# Motor_Driver2.net
KiCad netlist of a schematic drawn in EAGLE
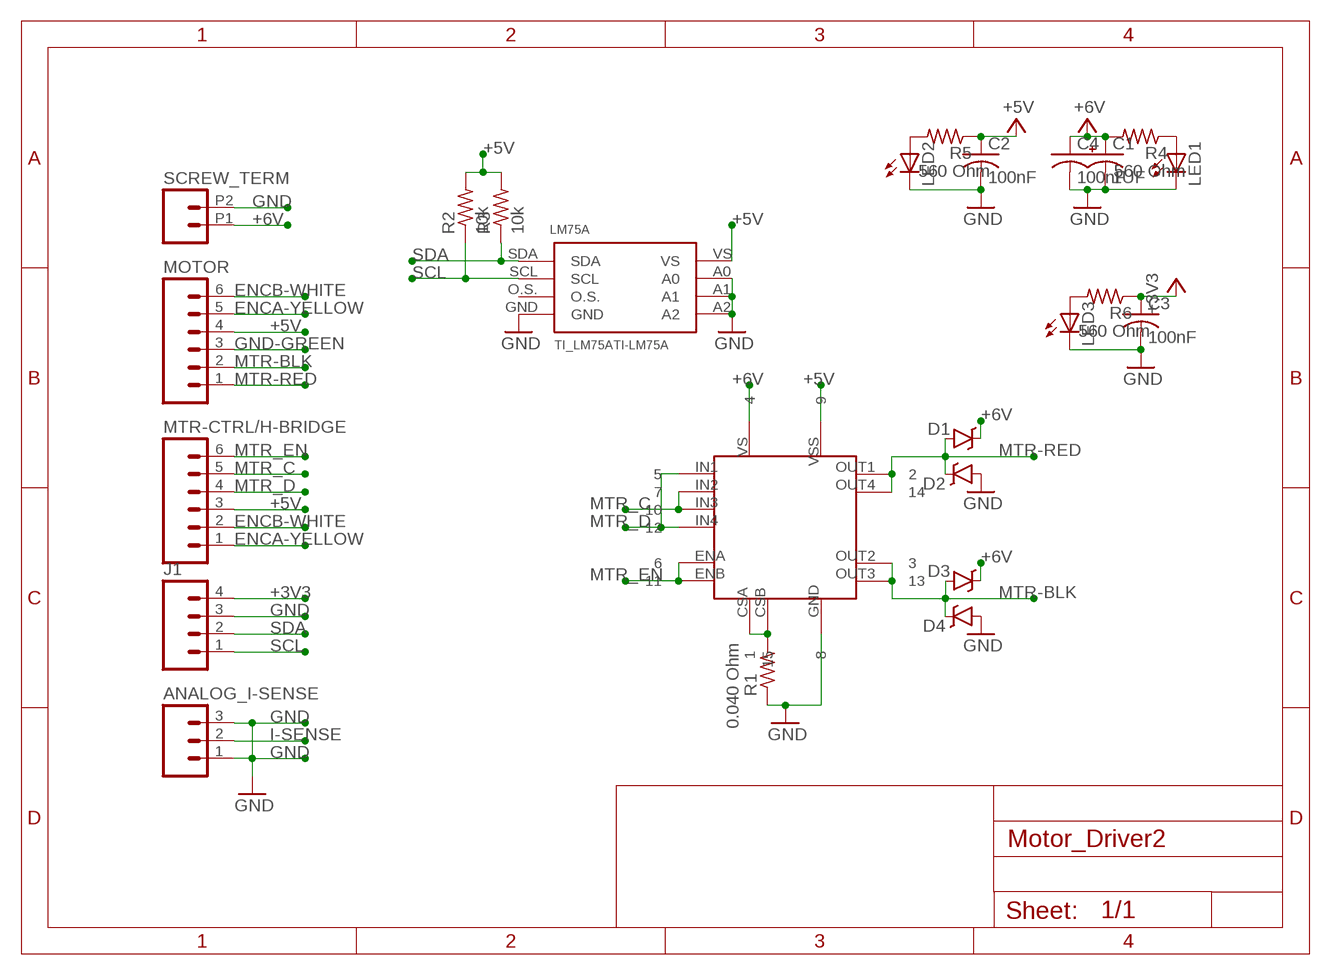
[diagram p0: schematic, sheet 1]

(export (version "E")
  (design (tool "Eeschema 10.0.6"))
  (components
    (comp (ref "ANALOG_I-SENSE")
      (value "M03PTH")
      (footprint "eagle-import:1X03")
      (libsource (lib "eagle-import") (part "M03PTH"))
    )
    (comp (ref "C1")
      (value "1UF")
      (footprint "eagle-import:CPOL-RADIAL-1UF-50V-KIT")
      (libsource (lib "eagle-import") (part "1UF-50V-20%(PTH)KIT"))
    )
    (comp (ref "C2")
      (value "100nF")
      (footprint "eagle-import:C1206")
      (libsource (lib "eagle-import") (part "C-USC1206"))
    )
    (comp (ref "C3")
      (value "100nF")
      (footprint "eagle-import:C1206")
      (libsource (lib "eagle-import") (part "C-USC1206"))
    )
    (comp (ref "C4")
      (value "100nF")
      (footprint "eagle-import:C1206")
      (libsource (lib "eagle-import") (part "C-USC1206"))
    )
    (comp (ref "D1")
      (value "B340A")
      (footprint "eagle-import:SMA-DIODE")
      (libsource (lib "eagle-import") (part "DIODE-SCHOTTKY-B340A"))
    )
    (comp (ref "D2")
      (value "B340A")
      (footprint "eagle-import:SMA-DIODE")
      (libsource (lib "eagle-import") (part "DIODE-SCHOTTKY-B340A"))
    )
    (comp (ref "D3")
      (value "B340A")
      (footprint "eagle-import:SMA-DIODE")
      (libsource (lib "eagle-import") (part "DIODE-SCHOTTKY-B340A"))
    )
    (comp (ref "D4")
      (value "B340A")
      (footprint "eagle-import:SMA-DIODE")
      (libsource (lib "eagle-import") (part "DIODE-SCHOTTKY-B340A"))
    )
    (comp (ref "J1")
      (value "M04PTH")
      (footprint "eagle-import:1X04")
      (libsource (lib "eagle-import") (part "M04PTH"))
    )
    (comp (ref "LED1")
      (value "LEDSMT1206")
      (footprint "eagle-import:1206")
      (libsource (lib "eagle-import") (part "LEDSMT1206"))
    )
    (comp (ref "LED2")
      (value "LEDSMT1206")
      (footprint "eagle-import:1206")
      (libsource (lib "eagle-import") (part "LEDSMT1206"))
    )
    (comp (ref "LED3")
      (value "LEDSMT1206")
      (footprint "eagle-import:1206")
      (libsource (lib "eagle-import") (part "LEDSMT1206"))
    )
    (comp (ref "LM75A")
      (value "TI_LM75ATI-LM75A")
      (footprint "eagle-import:TI_LM75A")
      (libsource (lib "eagle-import") (part "TI_LM75ATI-LM75A"))
    )
    (comp (ref "MOTOR")
      (value "M06SILK_FEMALE_PTH")
      (footprint "eagle-import:1X06")
      (libsource (lib "eagle-import") (part "M06SILK_FEMALE_PTH"))
    )
    (comp (ref "MTR-CTRL/H-BRIDGE")
      (value "M06SILK_FEMALE_PTH")
      (footprint "eagle-import:1X06")
      (libsource (lib "eagle-import") (part "M06SILK_FEMALE_PTH"))
    )
    (comp (ref "R1")
      (value "0.040 Ohm")
      (footprint "eagle-import:M0805")
      (libsource (lib "eagle-import") (part "R-US_M0805"))
    )
    (comp (ref "R2")
      (value "10k")
      (footprint "eagle-import:M1206")
      (libsource (lib "eagle-import") (part "R-US_M1206"))
    )
    (comp (ref "R3")
      (value "10k")
      (footprint "eagle-import:M1206")
      (libsource (lib "eagle-import") (part "R-US_M1206"))
    )
    (comp (ref "R4")
      (value "560 Ohm")
      (footprint "eagle-import:M0805")
      (libsource (lib "eagle-import") (part "R-US_M0805"))
    )
    (comp (ref "R5")
      (value "560 Ohm")
      (footprint "eagle-import:M0805")
      (libsource (lib "eagle-import") (part "R-US_M0805"))
    )
    (comp (ref "R6")
      (value "560 Ohm")
      (footprint "eagle-import:M0805")
      (libsource (lib "eagle-import") (part "R-US_M0805"))
    )
    (comp (ref "SCREW_TERM")
      (value "M022.54MM_SCREWTERM")
      (footprint "eagle-import:1X02_2.54_SCREWTERM")
      (libsource (lib "eagle-import") (part "M022.54MM_SCREWTERM"))
    )
    (comp (ref "U$1")
      (value "STL298N")
      (footprint "eagle-import:STL298N")
      (libsource (lib "eagle-import") (part "STL298N"))
    )
  )
  (nets
    (net (code "1") (name "+3V3") (class "Default")
      (node (ref "C3") (pin "1") (pinfunction "1_1") (pintype "passive"))
      (node (ref "J1") (pin "4") (pinfunction "4_4") (pintype "passive"))
      (node (ref "R6") (pin "1") (pinfunction "1_1") (pintype "passive"))
    )
    (net (code "2") (name "+5V") (class "Default")
      (node (ref "C2") (pin "1") (pinfunction "1_1") (pintype "passive"))
      (node (ref "LM75A") (pin "VS") (pinfunction "VS_VS") (pintype "bidirectional"))
      (node (ref "MOTOR") (pin "4") (pinfunction "4_4") (pintype "passive"))
      (node (ref "MTR-CTRL/H-BRIDGE") (pin "3") (pinfunction "3_3") (pintype "passive"))
      (node (ref "R2") (pin "2") (pinfunction "2_2") (pintype "passive"))
      (node (ref "R3") (pin "2") (pinfunction "2_2") (pintype "passive"))
      (node (ref "R5") (pin "1") (pinfunction "1_1") (pintype "passive"))
    )
    (net (code "3") (name "+6V") (class "Default")
      (node (ref "C1") (pin "1") (pinfunction "+_1") (pintype "passive"))
      (node (ref "C4") (pin "1") (pinfunction "1_1") (pintype "passive"))
      (node (ref "D1") (pin "C") (pinfunction "C_C") (pintype "passive"))
      (node (ref "D3") (pin "C") (pinfunction "C_C") (pintype "passive"))
      (node (ref "R4") (pin "2") (pinfunction "2_2") (pintype "passive"))
      (node (ref "SCREW_TERM") (pin "P1") (pinfunction "1_P1") (pintype "passive"))
    )
    (net (code "4") (name "/ENCA-YELLOW") (class "Default")
      (node (ref "MOTOR") (pin "5") (pinfunction "5_5") (pintype "passive"))
      (node (ref "MTR-CTRL/H-BRIDGE") (pin "1") (pinfunction "1_1") (pintype "passive"))
    )
    (net (code "5") (name "/ENCB-WHITE") (class "Default")
      (node (ref "MOTOR") (pin "6") (pinfunction "6_6") (pintype "passive"))
      (node (ref "MTR-CTRL/H-BRIDGE") (pin "2") (pinfunction "2_2") (pintype "passive"))
    )
    (net (code "6") (name "/GND-GREEN") (class "Default")
      (node (ref "MOTOR") (pin "3") (pinfunction "3_3") (pintype "passive"))
    )
    (net (code "7") (name "/I-SENSE") (class "Default")
      (node (ref "ANALOG_I-SENSE") (pin "2") (pinfunction "2_2") (pintype "passive"))
    )
    (net (code "8") (name "/MTR-BLK") (class "Default")
      (node (ref "D3") (pin "A") (pinfunction "A_A") (pintype "passive"))
      (node (ref "D4") (pin "C") (pinfunction "C_C") (pintype "passive"))
      (node (ref "MOTOR") (pin "2") (pinfunction "2_2") (pintype "passive"))
    )
    (net (code "9") (name "/MTR-RED") (class "Default")
      (node (ref "D1") (pin "A") (pinfunction "A_A") (pintype "passive"))
      (node (ref "D2") (pin "C") (pinfunction "C_C") (pintype "passive"))
      (node (ref "MOTOR") (pin "1") (pinfunction "1_1") (pintype "passive"))
    )
    (net (code "10") (name "/MTR_C") (class "Default")
      (node (ref "MTR-CTRL/H-BRIDGE") (pin "5") (pinfunction "5_5") (pintype "passive"))
    )
    (net (code "11") (name "/MTR_D") (class "Default")
      (node (ref "MTR-CTRL/H-BRIDGE") (pin "4") (pinfunction "4_4") (pintype "passive"))
    )
    (net (code "12") (name "/MTR_EN") (class "Default")
      (node (ref "MTR-CTRL/H-BRIDGE") (pin "6") (pinfunction "6_6") (pintype "passive"))
    )
    (net (code "13") (name "/SCL") (class "Default")
      (node (ref "J1") (pin "1") (pinfunction "1_1") (pintype "passive"))
      (node (ref "LM75A") (pin "SCL") (pinfunction "SCL_SCL") (pintype "bidirectional"))
      (node (ref "R2") (pin "1") (pinfunction "1_1") (pintype "passive"))
    )
    (net (code "14") (name "/SDA") (class "Default")
      (node (ref "J1") (pin "2") (pinfunction "2_2") (pintype "passive"))
      (node (ref "LM75A") (pin "SDA") (pinfunction "SDA_SDA") (pintype "bidirectional"))
      (node (ref "R3") (pin "1") (pinfunction "1_1") (pintype "passive"))
    )
    (net (code "15") (name "GND") (class "Default")
      (node (ref "ANALOG_I-SENSE") (pin "1") (pinfunction "1_1") (pintype "passive"))
      (node (ref "ANALOG_I-SENSE") (pin "3") (pinfunction "3_3") (pintype "passive"))
      (node (ref "C1") (pin "2") (pinfunction "-_2") (pintype "passive"))
      (node (ref "C2") (pin "2") (pinfunction "2_2") (pintype "passive"))
      (node (ref "C3") (pin "2") (pinfunction "2_2") (pintype "passive"))
      (node (ref "C4") (pin "2") (pinfunction "2_2") (pintype "passive"))
      (node (ref "D2") (pin "A") (pinfunction "A_A") (pintype "passive"))
      (node (ref "D4") (pin "A") (pinfunction "A_A") (pintype "passive"))
      (node (ref "J1") (pin "3") (pinfunction "3_3") (pintype "passive"))
      (node (ref "LED1") (pin "C") (pinfunction "C_C") (pintype "passive"))
      (node (ref "LED2") (pin "C") (pinfunction "C_C") (pintype "passive"))
      (node (ref "LED3") (pin "C") (pinfunction "C_C") (pintype "passive"))
      (node (ref "LM75A") (pin "A0") (pinfunction "A0_A0") (pintype "bidirectional"))
      (node (ref "LM75A") (pin "A1") (pinfunction "A1_A1") (pintype "bidirectional"))
      (node (ref "LM75A") (pin "A2") (pinfunction "A2_A2") (pintype "bidirectional"))
      (node (ref "LM75A") (pin "GND") (pinfunction "GND_GND") (pintype "bidirectional"))
      (node (ref "R1") (pin "1") (pinfunction "1_1") (pintype "passive"))
      (node (ref "SCREW_TERM") (pin "P2") (pinfunction "2_P2") (pintype "passive"))
    )
    (net (code "16") (name "Net-(LED1-PadA)") (class "Default")
      (node (ref "LED1") (pin "A") (pinfunction "A_A") (pintype "passive"))
      (node (ref "R4") (pin "1") (pinfunction "1_1") (pintype "passive"))
    )
    (net (code "17") (name "Net-(LED2-PadA)") (class "Default")
      (node (ref "LED2") (pin "A") (pinfunction "A_A") (pintype "passive"))
      (node (ref "R5") (pin "2") (pinfunction "2_2") (pintype "passive"))
    )
    (net (code "18") (name "Net-(LED3-PadA)") (class "Default")
      (node (ref "LED3") (pin "A") (pinfunction "A_A") (pintype "passive"))
      (node (ref "R6") (pin "2") (pinfunction "2_2") (pintype "passive"))
    )
    (net (code "19") (name "unconnected-(LM75A-PadO.S.)") (class "Default")
      (node (ref "LM75A") (pin "O.S.") (pinfunction "O.S._O.S.") (pintype "bidirectional"))
    )
    (net (code "20") (name "unconnected-(R1-Pad2)") (class "Default")
      (node (ref "R1") (pin "2") (pinfunction "2_2") (pintype "passive"))
    )
    (net (code "21") (name "unconnected-(U$1-1-PadCSA)") (class "Default")
      (node (ref "U$1") (pin "CSA") (pinfunction "1_CSA") (pintype "bidirectional"))
    )
    (net (code "22") (name "unconnected-(U$1-2-PadOUT1)") (class "Default")
      (node (ref "U$1") (pin "OUT1") (pinfunction "2_OUT1") (pintype "bidirectional"))
    )
    (net (code "23") (name "unconnected-(U$1-3-PadOUT2)") (class "Default")
      (node (ref "U$1") (pin "OUT2") (pinfunction "3_OUT2") (pintype "bidirectional"))
    )
    (net (code "24") (name "unconnected-(U$1-4-PadVS)") (class "Default")
      (node (ref "U$1") (pin "VS") (pinfunction "4_VS") (pintype "bidirectional"))
    )
    (net (code "25") (name "unconnected-(U$1-5-PadIN1)") (class "Default")
      (node (ref "U$1") (pin "IN1") (pinfunction "5_IN1") (pintype "bidirectional"))
    )
    (net (code "26") (name "unconnected-(U$1-6-PadENA)") (class "Default")
      (node (ref "U$1") (pin "ENA") (pinfunction "6_ENA") (pintype "bidirectional"))
    )
    (net (code "27") (name "unconnected-(U$1-7-PadIN2)") (class "Default")
      (node (ref "U$1") (pin "IN2") (pinfunction "7_IN2") (pintype "bidirectional"))
    )
    (net (code "28") (name "unconnected-(U$1-8-PadGND)") (class "Default")
      (node (ref "U$1") (pin "GND") (pinfunction "8_GND") (pintype "bidirectional"))
    )
    (net (code "29") (name "unconnected-(U$1-9-PadVSS)") (class "Default")
      (node (ref "U$1") (pin "VSS") (pinfunction "9_VSS") (pintype "bidirectional"))
    )
    (net (code "30") (name "unconnected-(U$1-10-PadIN3)") (class "Default")
      (node (ref "U$1") (pin "IN3") (pinfunction "10_IN3") (pintype "bidirectional"))
    )
    (net (code "31") (name "unconnected-(U$1-11-PadENB)") (class "Default")
      (node (ref "U$1") (pin "ENB") (pinfunction "11_ENB") (pintype "bidirectional"))
    )
    (net (code "32") (name "unconnected-(U$1-12-PadIN4)") (class "Default")
      (node (ref "U$1") (pin "IN4") (pinfunction "12_IN4") (pintype "bidirectional"))
    )
    (net (code "33") (name "unconnected-(U$1-13-PadOUT3)") (class "Default")
      (node (ref "U$1") (pin "OUT3") (pinfunction "13_OUT3") (pintype "bidirectional"))
    )
    (net (code "34") (name "unconnected-(U$1-14-PadOUT4)") (class "Default")
      (node (ref "U$1") (pin "OUT4") (pinfunction "14_OUT4") (pintype "bidirectional"))
    )
    (net (code "35") (name "unconnected-(U$1-15-PadCSB)") (class "Default")
      (node (ref "U$1") (pin "CSB") (pinfunction "15_CSB") (pintype "bidirectional"))
    )
  )
)
